# io-board-Bpod.net
KiCad netlist of a schematic drawn in EAGLE
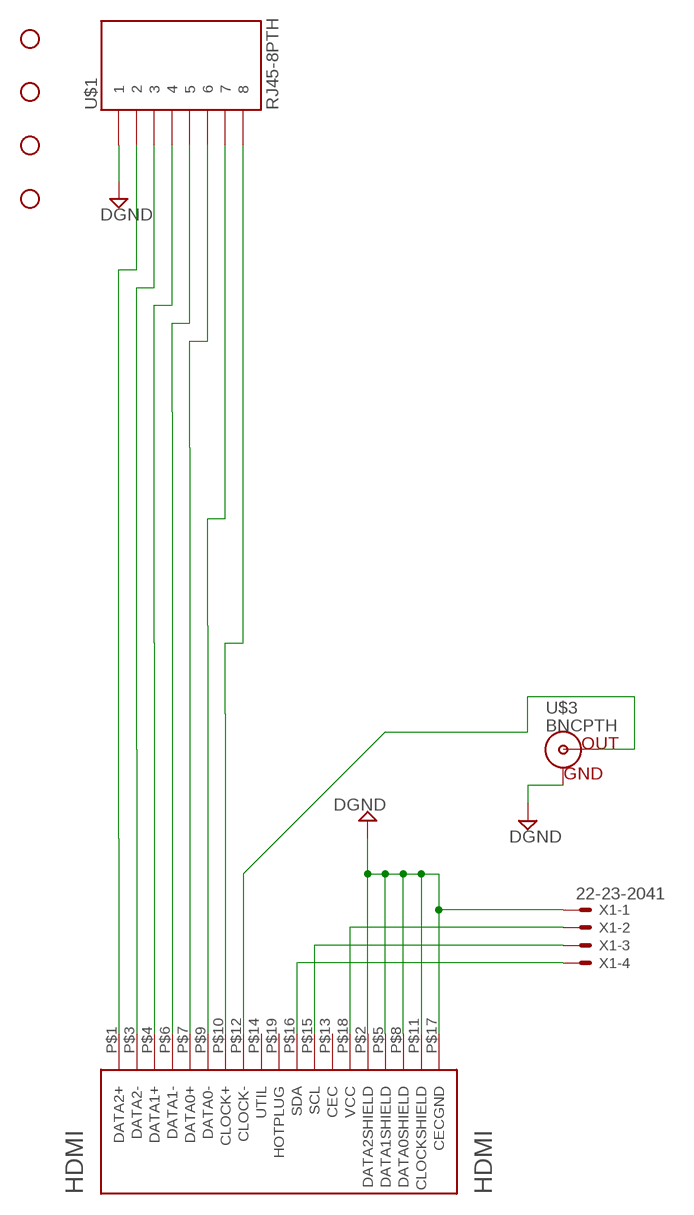
[diagram p0: schematic, sheet 1]

(export (version "E")
  (design (tool "Eeschema 10.0.6"))
  (components
    (comp (ref "HDMI")
      (value "HDMI")
      (footprint "eagle-import:HDMI_A")
      (libsource (lib "eagle-import") (part "HDMI"))
    )
    (comp (ref "STANDOFF1")
      (value "STAND-OFF")
      (footprint "eagle-import:STAND-OFF")
      (libsource (lib "eagle-import") (part "STAND-OFF"))
    )
    (comp (ref "STANDOFF2")
      (value "STAND-OFF")
      (footprint "eagle-import:STAND-OFF")
      (libsource (lib "eagle-import") (part "STAND-OFF"))
    )
    (comp (ref "STANDOFF3")
      (value "STAND-OFF")
      (footprint "eagle-import:STAND-OFF")
      (libsource (lib "eagle-import") (part "STAND-OFF"))
    )
    (comp (ref "STANDOFF4")
      (value "STAND-OFF")
      (footprint "eagle-import:STAND-OFF")
      (libsource (lib "eagle-import") (part "STAND-OFF"))
    )
    (comp (ref "U$1")
      (value "RJ45-8PTH")
      (footprint "eagle-import:RJ45-8")
      (libsource (lib "eagle-import") (part "RJ45-8PTH"))
    )
    (comp (ref "U$3")
      (value "BNCPTH")
      (footprint "eagle-import:BNC")
      (libsource (lib "eagle-import") (part "BNCPTH"))
    )
    (comp (ref "X1")
      (value "22-23-2041")
      (footprint "eagle-import:22-23-2041")
      (fields (field (name "MF") "MOLEX"))
      (libsource (lib "eagle-import") (part "22-23-2041"))
    )
  )
  (nets
    (net (code "1") (name "DGND") (class "Default")
      (node (ref "HDMI") (pin "P$11") (pinfunction "CLOCKSHIELD_P$11") (pintype "bidirectional"))
      (node (ref "HDMI") (pin "P$17") (pinfunction "CECGND_P$17") (pintype "bidirectional"))
      (node (ref "HDMI") (pin "P$2") (pinfunction "DATA2SHIELD_P$2") (pintype "bidirectional"))
      (node (ref "HDMI") (pin "P$5") (pinfunction "DATA1SHIELD_P$5") (pintype "bidirectional"))
      (node (ref "HDMI") (pin "P$8") (pinfunction "DATA0SHIELD_P$8") (pintype "bidirectional"))
      (node (ref "U$1") (pin "1") (pinfunction "1_1") (pintype "bidirectional"))
      (node (ref "U$3") (pin "GND") (pinfunction "GND_GND") (pintype "bidirectional"))
      (node (ref "X1") (pin "1") (pinfunction "S_1") (pintype "passive"))
    )
    (net (code "2") (name "Net-(HDMI-CLOCK+)") (class "Default")
      (node (ref "HDMI") (pin "P$10") (pinfunction "CLOCK+_P$10") (pintype "bidirectional"))
      (node (ref "U$1") (pin "8") (pinfunction "8_8") (pintype "bidirectional"))
    )
    (net (code "3") (name "Net-(HDMI-CLOCK-)") (class "Default")
      (node (ref "HDMI") (pin "P$12") (pinfunction "CLOCK-_P$12") (pintype "bidirectional"))
      (node (ref "U$3") (pin "S") (pinfunction "OUT_S") (pintype "bidirectional"))
    )
    (net (code "4") (name "Net-(HDMI-DATA0+)") (class "Default")
      (node (ref "HDMI") (pin "P$7") (pinfunction "DATA0+_P$7") (pintype "bidirectional"))
      (node (ref "U$1") (pin "6") (pinfunction "6_6") (pintype "bidirectional"))
    )
    (net (code "5") (name "Net-(HDMI-DATA0-)") (class "Default")
      (node (ref "HDMI") (pin "P$9") (pinfunction "DATA0-_P$9") (pintype "bidirectional"))
      (node (ref "U$1") (pin "7") (pinfunction "7_7") (pintype "bidirectional"))
    )
    (net (code "6") (name "Net-(HDMI-DATA1+)") (class "Default")
      (node (ref "HDMI") (pin "P$4") (pinfunction "DATA1+_P$4") (pintype "bidirectional"))
      (node (ref "U$1") (pin "4") (pinfunction "4_4") (pintype "bidirectional"))
    )
    (net (code "7") (name "Net-(HDMI-DATA1-)") (class "Default")
      (node (ref "HDMI") (pin "P$6") (pinfunction "DATA1-_P$6") (pintype "bidirectional"))
      (node (ref "U$1") (pin "5") (pinfunction "5_5") (pintype "bidirectional"))
    )
    (net (code "8") (name "Net-(HDMI-DATA2+)") (class "Default")
      (node (ref "HDMI") (pin "P$1") (pinfunction "DATA2+_P$1") (pintype "bidirectional"))
      (node (ref "U$1") (pin "2") (pinfunction "2_2") (pintype "bidirectional"))
    )
    (net (code "9") (name "Net-(HDMI-DATA2-)") (class "Default")
      (node (ref "HDMI") (pin "P$3") (pinfunction "DATA2-_P$3") (pintype "bidirectional"))
      (node (ref "U$1") (pin "3") (pinfunction "3_3") (pintype "bidirectional"))
    )
    (net (code "10") (name "Net-(HDMI-SCL)") (class "Default")
      (node (ref "HDMI") (pin "P$15") (pinfunction "SCL_P$15") (pintype "bidirectional"))
      (node (ref "X1") (pin "3") (pinfunction "S_3") (pintype "passive"))
    )
    (net (code "11") (name "Net-(HDMI-SDA)") (class "Default")
      (node (ref "HDMI") (pin "P$16") (pinfunction "SDA_P$16") (pintype "bidirectional"))
      (node (ref "X1") (pin "4") (pinfunction "S_4") (pintype "passive"))
    )
    (net (code "12") (name "Net-(HDMI-VCC)") (class "Default")
      (node (ref "HDMI") (pin "P$18") (pinfunction "VCC_P$18") (pintype "bidirectional"))
      (node (ref "X1") (pin "2") (pinfunction "S_2") (pintype "passive"))
    )
    (net (code "13") (name "unconnected-(HDMI-CEC-PadP$13)") (class "Default")
      (node (ref "HDMI") (pin "P$13") (pinfunction "CEC_P$13") (pintype "bidirectional"))
    )
    (net (code "14") (name "unconnected-(HDMI-HOTPLUG-PadP$19)") (class "Default")
      (node (ref "HDMI") (pin "P$19") (pinfunction "HOTPLUG_P$19") (pintype "bidirectional"))
    )
    (net (code "15") (name "unconnected-(HDMI-UTIL-PadP$14)") (class "Default")
      (node (ref "HDMI") (pin "P$14") (pinfunction "UTIL_P$14") (pintype "bidirectional"))
    )
  )
)
